# untitled.net
KiCad netlist of a schematic drawn in EAGLE
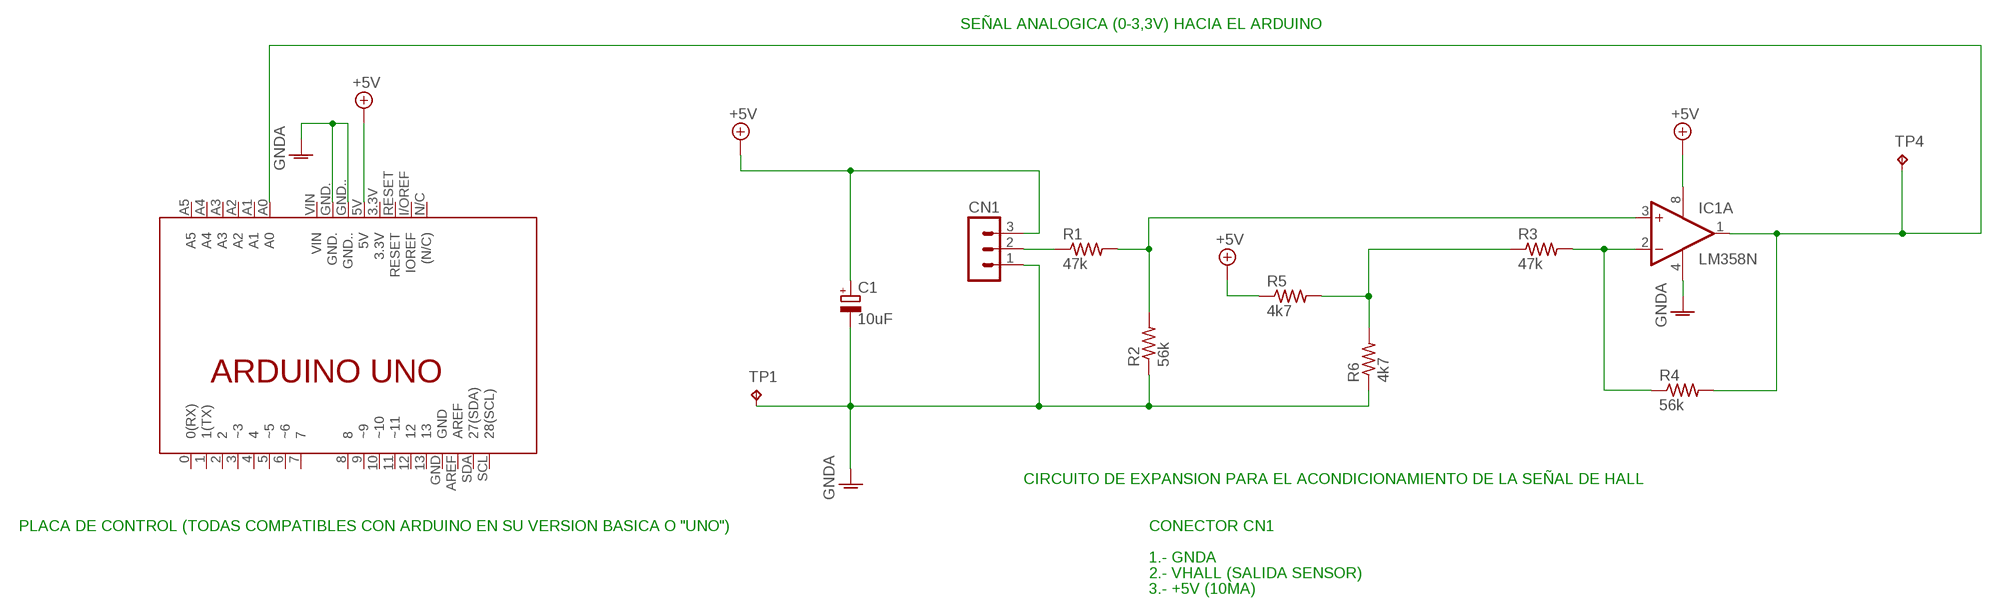
[diagram p0: schematic, sheet 1]

(export (version "E")
  (design (tool "Eeschema 10.0.6"))
  (components
    (comp (ref "C1")
      (value "10uF")
      (footprint "eagle-import:E5-10,5")
      (libsource (lib "eagle-import") (part "CPOL-EUE5-10.5"))
    )
    (comp (ref "CN1")
      (value "MA03-1")
      (footprint "eagle-import:MA03-1")
      (libsource (lib "eagle-import") (part "MA03-1"))
    )
    (comp (ref "IC1")
      (value "LM358N")
      (footprint "eagle-import:DIL08")
      (libsource (lib "eagle-import") (part "LM358N"))
    )
    (comp (ref "R1")
      (value "47k")
      (footprint "eagle-import:R1206W")
      (libsource (lib "eagle-import") (part "R-US_R1206W"))
    )
    (comp (ref "R2")
      (value "56k")
      (footprint "eagle-import:R1206W")
      (libsource (lib "eagle-import") (part "R-US_R1206W"))
    )
    (comp (ref "R3")
      (value "47k")
      (footprint "eagle-import:R1206W")
      (libsource (lib "eagle-import") (part "R-US_R1206W"))
    )
    (comp (ref "R4")
      (value "56k")
      (footprint "eagle-import:R1206W")
      (libsource (lib "eagle-import") (part "R-US_R1206W"))
    )
    (comp (ref "R5")
      (value "4k7")
      (footprint "eagle-import:R1206W")
      (libsource (lib "eagle-import") (part "R-US_R1206W"))
    )
    (comp (ref "R6")
      (value "4k7")
      (footprint "eagle-import:R1206W")
      (libsource (lib "eagle-import") (part "R-US_R1206W"))
    )
    (comp (ref "TP1")
      (value "TPPAD1-13Y")
      (footprint "eagle-import:P1-13Y")
      (libsource (lib "eagle-import") (part "TPPAD1-13Y"))
    )
    (comp (ref "TP4")
      (value "TPPAD1-13Y")
      (footprint "eagle-import:P1-13Y")
      (libsource (lib "eagle-import") (part "TPPAD1-13Y"))
    )
    (comp (ref "U$1")
      (value "ARDUINO_UNO_SPL")
      (footprint "eagle-import:ARDUINO_UNO_REC")
      (libsource (lib "eagle-import") (part "ARDUINO_UNO_SPL"))
    )
  )
  (nets
    (net (code "1") (name "+5V") (class "Default")
      (node (ref "C1") (pin "+") (pinfunction "+_+") (pintype "passive"))
      (node (ref "CN1") (pin "3") (pinfunction "3_3") (pintype "passive"))
      (node (ref "IC1") (pin "8") (pinfunction "V+_8") (pintype "power_in"))
      (node (ref "R5") (pin "1") (pinfunction "1_1") (pintype "passive"))
      (node (ref "U$1") (pin "5V") (pinfunction "5V_5V") (pintype "bidirectional"))
    )
    (net (code "2") (name "GNDA") (class "Default")
      (node (ref "C1") (pin "-") (pinfunction "-_-") (pintype "passive"))
      (node (ref "CN1") (pin "1") (pinfunction "1_1") (pintype "passive"))
      (node (ref "IC1") (pin "4") (pinfunction "V-_4") (pintype "power_in"))
      (node (ref "R2") (pin "1") (pinfunction "1_1") (pintype "passive"))
      (node (ref "R6") (pin "1") (pinfunction "1_1") (pintype "passive"))
      (node (ref "TP1") (pin "TP") (pinfunction "TP_TP") (pintype "input"))
      (node (ref "U$1") (pin "GND.") (pinfunction "GND._GND.") (pintype "bidirectional"))
      (node (ref "U$1") (pin "GND..") (pinfunction "GND.._GND..") (pintype "bidirectional"))
    )
    (net (code "3") (name "Net-(CN1-Pad2)") (class "Default")
      (node (ref "CN1") (pin "2") (pinfunction "2_2") (pintype "passive"))
      (node (ref "R1") (pin "1") (pinfunction "1_1") (pintype "passive"))
    )
    (net (code "4") (name "Net-(IC1A-+IN)") (class "Default")
      (node (ref "IC1") (pin "3") (pinfunction "+IN_3") (pintype "input"))
      (node (ref "R1") (pin "2") (pinfunction "2_2") (pintype "passive"))
      (node (ref "R2") (pin "2") (pinfunction "2_2") (pintype "passive"))
    )
    (net (code "5") (name "Net-(IC1A--IN)") (class "Default")
      (node (ref "IC1") (pin "2") (pinfunction "-IN_2") (pintype "input"))
      (node (ref "R3") (pin "2") (pinfunction "2_2") (pintype "passive"))
      (node (ref "R4") (pin "1") (pinfunction "1_1") (pintype "passive"))
    )
    (net (code "6") (name "Net-(IC1A-OUT)") (class "Default")
      (node (ref "IC1") (pin "1") (pinfunction "OUT_1") (pintype "output"))
      (node (ref "R4") (pin "2") (pinfunction "2_2") (pintype "passive"))
      (node (ref "TP4") (pin "TP") (pinfunction "TP_TP") (pintype "input"))
      (node (ref "U$1") (pin "A0") (pinfunction "A0_A0") (pintype "bidirectional"))
    )
    (net (code "7") (name "Net-(R3-Pad1)") (class "Default")
      (node (ref "R3") (pin "1") (pinfunction "1_1") (pintype "passive"))
      (node (ref "R5") (pin "2") (pinfunction "2_2") (pintype "passive"))
      (node (ref "R6") (pin "2") (pinfunction "2_2") (pintype "passive"))
    )
    (net (code "8") (name "unconnected-(U$1-(N{slash}C)-PadN{slash}C)") (class "Default")
      (node (ref "U$1") (pin "N/C") (pinfunction "(N/C)_N/C") (pintype "bidirectional"))
    )
    (net (code "9") (name "unconnected-(U$1-0(RX)-Pad0)") (class "Default")
      (node (ref "U$1") (pin "0") (pinfunction "0(RX)_0") (pintype "bidirectional"))
    )
    (net (code "10") (name "unconnected-(U$1-1(TX)-Pad1)") (class "Default")
      (node (ref "U$1") (pin "1") (pinfunction "1(TX)_1") (pintype "bidirectional"))
    )
    (net (code "11") (name "unconnected-(U$1-27(SDA)-PadSDA)") (class "Default")
      (node (ref "U$1") (pin "SDA") (pinfunction "27(SDA)_SDA") (pintype "bidirectional"))
    )
    (net (code "12") (name "unconnected-(U$1-28(SCL)-PadSCL)") (class "Default")
      (node (ref "U$1") (pin "SCL") (pinfunction "28(SCL)_SCL") (pintype "bidirectional"))
    )
    (net (code "13") (name "unconnected-(U$1-IOREF-PadI{slash}OREF)") (class "Default")
      (node (ref "U$1") (pin "I/OREF") (pinfunction "IOREF_I/OREF") (pintype "bidirectional"))
    )
    (net (code "14") (name "unconnected-(U$1-Pad2)") (class "Default")
      (node (ref "U$1") (pin "2") (pinfunction "2_2") (pintype "bidirectional"))
    )
    (net (code "15") (name "unconnected-(U$1-Pad3.3V)") (class "Default")
      (node (ref "U$1") (pin "3.3V") (pinfunction "3.3V_3.3V") (pintype "bidirectional"))
    )
    (net (code "16") (name "unconnected-(U$1-Pad4)") (class "Default")
      (node (ref "U$1") (pin "4") (pinfunction "4_4") (pintype "bidirectional"))
    )
    (net (code "17") (name "unconnected-(U$1-Pad7)") (class "Default")
      (node (ref "U$1") (pin "7") (pinfunction "7_7") (pintype "bidirectional"))
    )
    (net (code "18") (name "unconnected-(U$1-Pad8)") (class "Default")
      (node (ref "U$1") (pin "8") (pinfunction "8_8") (pintype "bidirectional"))
    )
    (net (code "19") (name "unconnected-(U$1-Pad12)") (class "Default")
      (node (ref "U$1") (pin "12") (pinfunction "12_12") (pintype "bidirectional"))
    )
    (net (code "20") (name "unconnected-(U$1-Pad13)") (class "Default")
      (node (ref "U$1") (pin "13") (pinfunction "13_13") (pintype "bidirectional"))
    )
    (net (code "21") (name "unconnected-(U$1-PadA1)") (class "Default")
      (node (ref "U$1") (pin "A1") (pinfunction "A1_A1") (pintype "bidirectional"))
    )
    (net (code "22") (name "unconnected-(U$1-PadA2)") (class "Default")
      (node (ref "U$1") (pin "A2") (pinfunction "A2_A2") (pintype "bidirectional"))
    )
    (net (code "23") (name "unconnected-(U$1-PadA3)") (class "Default")
      (node (ref "U$1") (pin "A3") (pinfunction "A3_A3") (pintype "bidirectional"))
    )
    (net (code "24") (name "unconnected-(U$1-PadA4)") (class "Default")
      (node (ref "U$1") (pin "A4") (pinfunction "A4_A4") (pintype "bidirectional"))
    )
    (net (code "25") (name "unconnected-(U$1-PadA5)") (class "Default")
      (node (ref "U$1") (pin "A5") (pinfunction "A5_A5") (pintype "bidirectional"))
    )
    (net (code "26") (name "unconnected-(U$1-PadAREF)") (class "Default")
      (node (ref "U$1") (pin "AREF") (pinfunction "AREF_AREF") (pintype "bidirectional"))
    )
    (net (code "27") (name "unconnected-(U$1-PadGND)") (class "Default")
      (node (ref "U$1") (pin "GND") (pinfunction "GND_GND") (pintype "bidirectional"))
    )
    (net (code "28") (name "unconnected-(U$1-PadRESET)") (class "Default")
      (node (ref "U$1") (pin "RESET") (pinfunction "RESET_RESET") (pintype "bidirectional"))
    )
    (net (code "29") (name "unconnected-(U$1-PadVIN)") (class "Default")
      (node (ref "U$1") (pin "VIN") (pinfunction "VIN_VIN") (pintype "bidirectional"))
    )
    (net (code "30") (name "unconnected-(U$1-~{3}-Pad3)") (class "Default")
      (node (ref "U$1") (pin "3") (pinfunction "~{3}_3") (pintype "bidirectional"))
    )
    (net (code "31") (name "unconnected-(U$1-~{5}-Pad5)") (class "Default")
      (node (ref "U$1") (pin "5") (pinfunction "~{5}_5") (pintype "bidirectional"))
    )
    (net (code "32") (name "unconnected-(U$1-~{6}-Pad6)") (class "Default")
      (node (ref "U$1") (pin "6") (pinfunction "~{6}_6") (pintype "bidirectional"))
    )
    (net (code "33") (name "unconnected-(U$1-~{9}-Pad9)") (class "Default")
      (node (ref "U$1") (pin "9") (pinfunction "~{9}_9") (pintype "bidirectional"))
    )
    (net (code "34") (name "unconnected-(U$1-~{10}-Pad10)") (class "Default")
      (node (ref "U$1") (pin "10") (pinfunction "~{10}_10") (pintype "bidirectional"))
    )
    (net (code "35") (name "unconnected-(U$1-~{11}-Pad11)") (class "Default")
      (node (ref "U$1") (pin "11") (pinfunction "~{11}_11") (pintype "bidirectional"))
    )
  )
)
